# Analog_Input_Noise_Canceller.net
KiCad netlist of a schematic drawn in Altium Designer
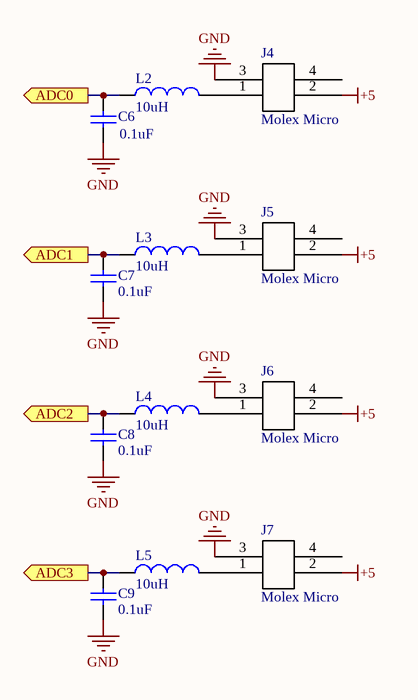
[diagram p0: Analog Input Noise Canceller.SchDoc]

(export (version "E")
  (design (tool "Eeschema 10.0.6"))
  (components
    (comp (ref "C6")
      (value "0.1uF")
      (footprint "CAPC2013X94X50LL20T25")
      (description "Chip Capacitor, 0.1 uF, +/- 5%, 50 V, -55 to 125 degC, 0805 (2012 Metric), RoHS, Tape and Reel")
      (fields (field (name "TOLERANCE") "5%") (field (name "MANUFACTURER") "AVX"))
      (libsource (lib "Altium Content Vault") (part "CAP-NP-2"))
    )
    (comp (ref "C7")
      (value "0.1uF")
      (footprint "CAPC2013X94X50LL20T25")
      (description "Chip Capacitor, 0.1 uF, +/- 5%, 50 V, -55 to 125 degC, 0805 (2012 Metric), RoHS, Tape and Reel")
      (fields (field (name "TOLERANCE") "5%") (field (name "MANUFACTURER") "AVX"))
      (libsource (lib "Altium Content Vault") (part "CAP-NP-2"))
    )
    (comp (ref "C8")
      (value "0.1uF")
      (footprint "CAPC2013X94X50LL20T25")
      (description "Chip Capacitor, 0.1 uF, +/- 5%, 50 V, -55 to 125 degC, 0805 (2012 Metric), RoHS, Tape and Reel")
      (fields (field (name "TOLERANCE") "5%") (field (name "MANUFACTURER") "AVX"))
      (libsource (lib "Altium Content Vault") (part "CAP-NP-2"))
    )
    (comp (ref "C9")
      (value "0.1uF")
      (footprint "CAPC2013X94X50LL20T25")
      (description "Chip Capacitor, 0.1 uF, +/- 5%, 50 V, -55 to 125 degC, 0805 (2012 Metric), RoHS, Tape and Reel")
      (fields (field (name "TOLERANCE") "5%") (field (name "MANUFACTURER") "AVX"))
      (libsource (lib "Altium Content Vault") (part "CAP-NP-2"))
    )
    (comp (ref "J4")
      (value "Molex Micro")
      (footprint "0430450427")
      (description "Molex micro-fit 3.0, P/N 0430450427")
      (libsource (lib "Husky Robotics Standard Library 2019-2020") (part "Molex micro-fit 4-pin (dual row schematic)"))
    )
    (comp (ref "J5")
      (value "Molex Micro")
      (footprint "0430450427")
      (description "Molex micro-fit 3.0, P/N 0430450427")
      (libsource (lib "Husky Robotics Standard Library 2019-2020") (part "Molex micro-fit 4-pin (dual row schematic)"))
    )
    (comp (ref "J6")
      (value "Molex Micro")
      (footprint "0430450427")
      (description "Molex micro-fit 3.0, P/N 0430450427")
      (libsource (lib "Husky Robotics Standard Library 2019-2020") (part "Molex micro-fit 4-pin (dual row schematic)"))
    )
    (comp (ref "J7")
      (value "Molex Micro")
      (footprint "0430450427")
      (description "Molex micro-fit 3.0, P/N 0430450427")
      (libsource (lib "Husky Robotics Standard Library 2019-2020") (part "Molex micro-fit 4-pin (dual row schematic)"))
    )
    (comp (ref "L2")
      (value "10uH")
      (footprint "TDK-IND0805-125_V")
      (description "Multilayer Inductor, 10 uH, ±20%, 300 mOhm, 50MHz, 0805(2012)")
      (fields (field (name "PARTNUMBER") "MLZ2012N100LT"))
      (libsource (lib "Altium Content Vault") (part "TDK-IND_INDUCTOR-2"))
    )
    (comp (ref "L3")
      (value "10uH")
      (footprint "TDK-IND0805-125_V")
      (description "Multilayer Inductor, 10 uH, ±20%, 300 mOhm, 50MHz, 0805(2012)")
      (fields (field (name "PARTNUMBER") "MLZ2012N100LT"))
      (libsource (lib "Altium Content Vault") (part "TDK-IND_INDUCTOR-2"))
    )
    (comp (ref "L4")
      (value "10uH")
      (footprint "TDK-IND0805-125_V")
      (description "Multilayer Inductor, 10 uH, ±20%, 300 mOhm, 50MHz, 0805(2012)")
      (fields (field (name "PARTNUMBER") "MLZ2012N100LT"))
      (libsource (lib "Altium Content Vault") (part "TDK-IND_INDUCTOR-2"))
    )
    (comp (ref "L5")
      (value "10uH")
      (footprint "TDK-IND0805-125_V")
      (description "Multilayer Inductor, 10 uH, ±20%, 300 mOhm, 50MHz, 0805(2012)")
      (fields (field (name "PARTNUMBER") "MLZ2012N100LT"))
      (libsource (lib "Altium Content Vault") (part "TDK-IND_INDUCTOR-2"))
    )
  )
  (nets
    (net (code "1") (name "+5") (class "Default")
      (node (ref "J4") (pin "2") (pintype "passive"))
      (node (ref "J5") (pin "2") (pintype "passive"))
      (node (ref "J6") (pin "2") (pintype "passive"))
      (node (ref "J7") (pin "2") (pintype "passive"))
    )
    (net (code "2") (name "/ADC0") (class "Default")
      (node (ref "C6") (pin "1") (pinfunction "1_1") (pintype "passive"))
      (node (ref "L2") (pin "1") (pinfunction "1_1") (pintype "passive"))
    )
    (net (code "3") (name "/ADC1") (class "Default")
      (node (ref "C7") (pin "1") (pinfunction "1_1") (pintype "passive"))
      (node (ref "L3") (pin "1") (pinfunction "1_1") (pintype "passive"))
    )
    (net (code "4") (name "/ADC2") (class "Default")
      (node (ref "C8") (pin "2") (pinfunction "2_2") (pintype "passive"))
      (node (ref "L4") (pin "1") (pinfunction "1_1") (pintype "passive"))
    )
    (net (code "5") (name "/ADC3") (class "Default")
      (node (ref "C9") (pin "2") (pinfunction "2_2") (pintype "passive"))
      (node (ref "L5") (pin "1") (pinfunction "1_1") (pintype "passive"))
    )
    (net (code "6") (name "GND") (class "Default")
      (node (ref "C6") (pin "2") (pinfunction "2_2") (pintype "passive"))
      (node (ref "C7") (pin "2") (pinfunction "2_2") (pintype "passive"))
      (node (ref "C8") (pin "1") (pinfunction "1_1") (pintype "passive"))
      (node (ref "C9") (pin "1") (pinfunction "1_1") (pintype "passive"))
      (node (ref "J4") (pin "3") (pintype "passive"))
      (node (ref "J5") (pin "3") (pintype "passive"))
      (node (ref "J6") (pin "3") (pintype "passive"))
      (node (ref "J7") (pin "3") (pintype "passive"))
    )
    (net (code "7") (name "Net-(J4-Pad1)") (class "Default")
      (node (ref "J4") (pin "1") (pintype "passive"))
      (node (ref "L2") (pin "2") (pinfunction "2_2") (pintype "passive"))
    )
    (net (code "8") (name "Net-(J5-Pad1)") (class "Default")
      (node (ref "J5") (pin "1") (pintype "passive"))
      (node (ref "L3") (pin "2") (pinfunction "2_2") (pintype "passive"))
    )
    (net (code "9") (name "Net-(J6-Pad1)") (class "Default")
      (node (ref "J6") (pin "1") (pintype "passive"))
      (node (ref "L4") (pin "2") (pinfunction "2_2") (pintype "passive"))
    )
    (net (code "10") (name "Net-(J7-Pad1)") (class "Default")
      (node (ref "J7") (pin "1") (pintype "passive"))
      (node (ref "L5") (pin "2") (pinfunction "2_2") (pintype "passive"))
    )
    (net (code "11") (name "unconnected-(J4-Pad4)") (class "Default")
      (node (ref "J4") (pin "4") (pintype "passive"))
    )
    (net (code "12") (name "unconnected-(J5-Pad4)") (class "Default")
      (node (ref "J5") (pin "4") (pintype "passive"))
    )
    (net (code "13") (name "unconnected-(J6-Pad4)") (class "Default")
      (node (ref "J6") (pin "4") (pintype "passive"))
    )
    (net (code "14") (name "unconnected-(J7-Pad4)") (class "Default")
      (node (ref "J7") (pin "4") (pintype "passive"))
    )
  )
)
